# sensor.net
KiCad netlist of a schematic drawn in EAGLE
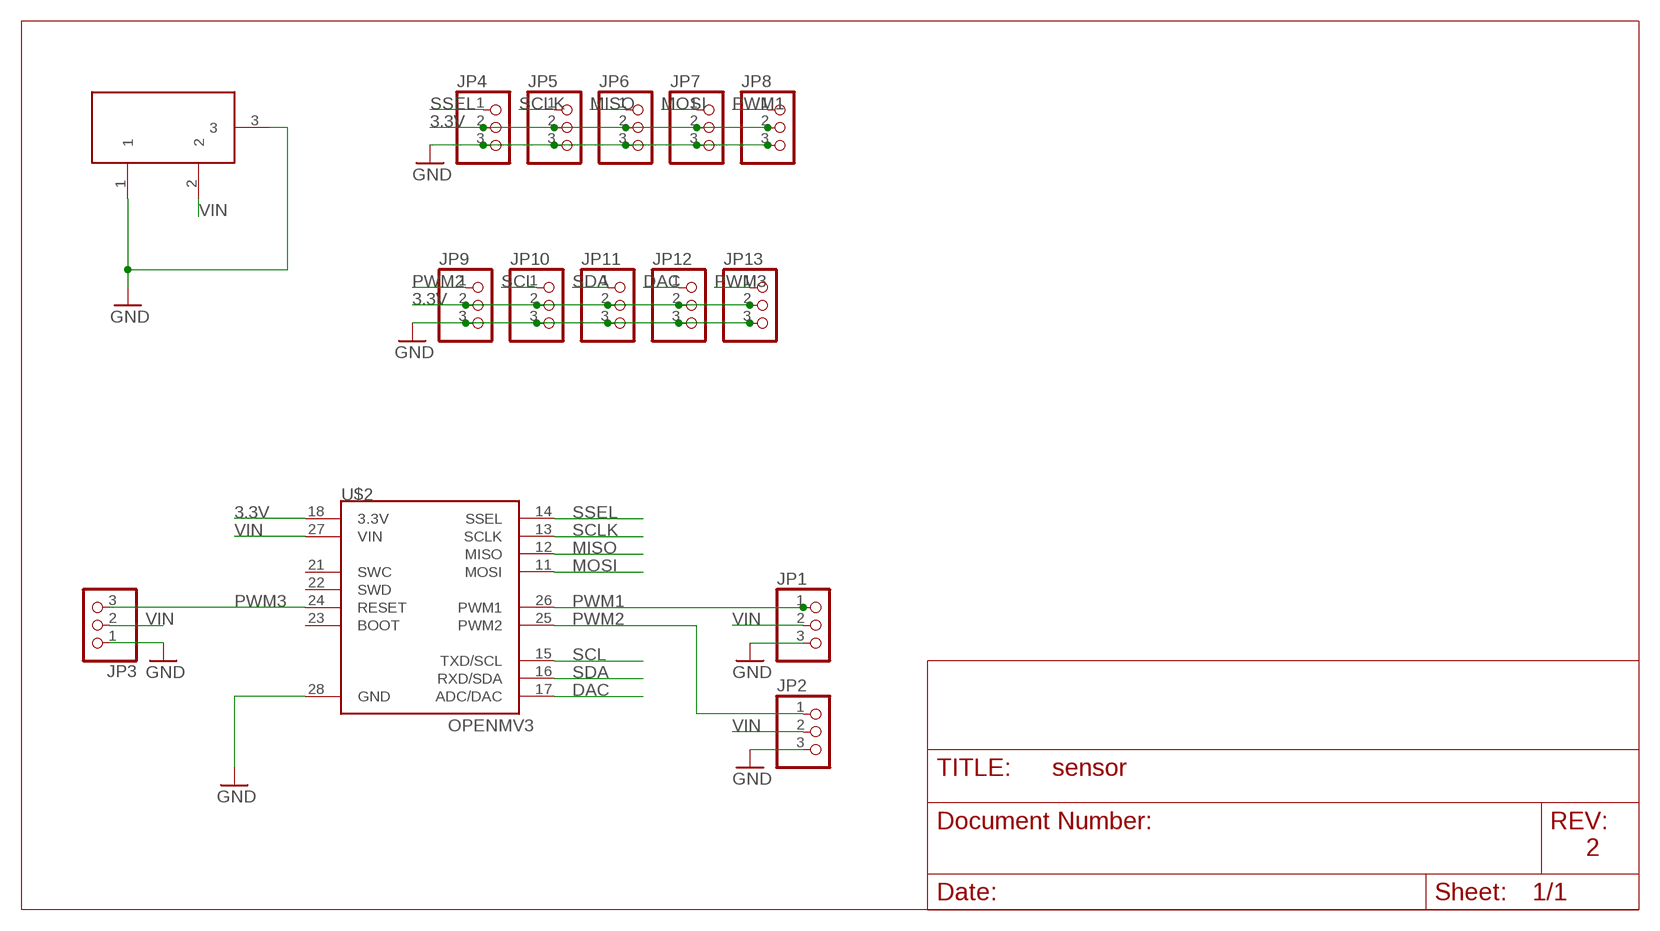
[diagram p0: schematic, sheet 1]

(export (version "E")
  (design (tool "Eeschema 10.0.6"))
  (components
    (comp (ref "JP1")
      (value "PINHEAD_PINHD-1X3")
      (footprint "eagle-import:PINHEAD_1X03")
      (libsource (lib "eagle-import") (part "PINHEAD_PINHD-1X3"))
    )
    (comp (ref "JP2")
      (value "PINHEAD_PINHD-1X3")
      (footprint "eagle-import:PINHEAD_1X03")
      (libsource (lib "eagle-import") (part "PINHEAD_PINHD-1X3"))
    )
    (comp (ref "JP3")
      (value "PINHEAD_PINHD-1X3")
      (footprint "eagle-import:PINHEAD_1X03")
      (libsource (lib "eagle-import") (part "PINHEAD_PINHD-1X3"))
    )
    (comp (ref "JP4")
      (value "PINHEAD_PINHD-1X3")
      (footprint "eagle-import:PINHEAD_1X03")
      (libsource (lib "eagle-import") (part "PINHEAD_PINHD-1X3"))
    )
    (comp (ref "JP5")
      (value "PINHEAD_PINHD-1X3")
      (footprint "eagle-import:PINHEAD_1X03")
      (libsource (lib "eagle-import") (part "PINHEAD_PINHD-1X3"))
    )
    (comp (ref "JP6")
      (value "PINHEAD_PINHD-1X3")
      (footprint "eagle-import:PINHEAD_1X03")
      (libsource (lib "eagle-import") (part "PINHEAD_PINHD-1X3"))
    )
    (comp (ref "JP7")
      (value "PINHEAD_PINHD-1X3")
      (footprint "eagle-import:PINHEAD_1X03")
      (libsource (lib "eagle-import") (part "PINHEAD_PINHD-1X3"))
    )
    (comp (ref "JP8")
      (value "PINHEAD_PINHD-1X3")
      (footprint "eagle-import:PINHEAD_1X03")
      (libsource (lib "eagle-import") (part "PINHEAD_PINHD-1X3"))
    )
    (comp (ref "JP9")
      (value "PINHEAD_PINHD-1X3")
      (footprint "eagle-import:PINHEAD_1X03")
      (libsource (lib "eagle-import") (part "PINHEAD_PINHD-1X3"))
    )
    (comp (ref "JP10")
      (value "PINHEAD_PINHD-1X3")
      (footprint "eagle-import:PINHEAD_1X03")
      (libsource (lib "eagle-import") (part "PINHEAD_PINHD-1X3"))
    )
    (comp (ref "JP11")
      (value "PINHEAD_PINHD-1X3")
      (footprint "eagle-import:PINHEAD_1X03")
      (libsource (lib "eagle-import") (part "PINHEAD_PINHD-1X3"))
    )
    (comp (ref "JP12")
      (value "PINHEAD_PINHD-1X3")
      (footprint "eagle-import:PINHEAD_1X03")
      (libsource (lib "eagle-import") (part "PINHEAD_PINHD-1X3"))
    )
    (comp (ref "JP13")
      (value "PINHEAD_PINHD-1X3")
      (footprint "eagle-import:PINHEAD_1X03")
      (libsource (lib "eagle-import") (part "PINHEAD_PINHD-1X3"))
    )
    (comp (ref "U$2")
      (value "OPENMV3")
      (footprint "eagle-import:OPENMV3")
      (libsource (lib "eagle-import") (part "OPENMV3"))
    )
    (comp (ref "X1")
      (value "DC21MMX")
      (footprint "eagle-import:DC-21MM")
      (libsource (lib "eagle-import") (part "DC21MMX"))
    )
  )
  (nets
    (net (code "1") (name "/3.3V") (class "Default")
      (node (ref "JP10") (pin "2") (pinfunction "2_2") (pintype "passive"))
      (node (ref "JP11") (pin "2") (pinfunction "2_2") (pintype "passive"))
      (node (ref "JP12") (pin "2") (pinfunction "2_2") (pintype "passive"))
      (node (ref "JP13") (pin "2") (pinfunction "2_2") (pintype "passive"))
      (node (ref "JP4") (pin "2") (pinfunction "2_2") (pintype "passive"))
      (node (ref "JP5") (pin "2") (pinfunction "2_2") (pintype "passive"))
      (node (ref "JP6") (pin "2") (pinfunction "2_2") (pintype "passive"))
      (node (ref "JP7") (pin "2") (pinfunction "2_2") (pintype "passive"))
      (node (ref "JP8") (pin "2") (pinfunction "2_2") (pintype "passive"))
      (node (ref "JP9") (pin "2") (pinfunction "2_2") (pintype "passive"))
      (node (ref "U$2") (pin "18") (pinfunction "3.3V_18") (pintype "power_in"))
    )
    (net (code "2") (name "/DAC") (class "Default")
      (node (ref "JP12") (pin "1") (pinfunction "1_1") (pintype "passive"))
      (node (ref "U$2") (pin "17") (pinfunction "ADC/DAC_17") (pintype "bidirectional"))
    )
    (net (code "3") (name "/MISO") (class "Default")
      (node (ref "JP6") (pin "1") (pinfunction "1_1") (pintype "passive"))
      (node (ref "U$2") (pin "12") (pinfunction "MISO_12") (pintype "bidirectional"))
    )
    (net (code "4") (name "/MOSI") (class "Default")
      (node (ref "JP7") (pin "1") (pinfunction "1_1") (pintype "passive"))
      (node (ref "U$2") (pin "11") (pinfunction "MOSI_11") (pintype "bidirectional"))
    )
    (net (code "5") (name "/PWM1") (class "Default")
      (node (ref "JP1") (pin "1") (pinfunction "1_1") (pintype "passive"))
      (node (ref "JP8") (pin "1") (pinfunction "1_1") (pintype "passive"))
      (node (ref "U$2") (pin "26") (pinfunction "PWM1_26") (pintype "bidirectional"))
    )
    (net (code "6") (name "/PWM2") (class "Default")
      (node (ref "JP2") (pin "1") (pinfunction "1_1") (pintype "passive"))
      (node (ref "JP9") (pin "1") (pinfunction "1_1") (pintype "passive"))
      (node (ref "U$2") (pin "25") (pinfunction "PWM2_25") (pintype "bidirectional"))
    )
    (net (code "7") (name "/PWM3") (class "Default")
      (node (ref "JP13") (pin "1") (pinfunction "1_1") (pintype "passive"))
      (node (ref "JP3") (pin "3") (pinfunction "3_3") (pintype "passive"))
      (node (ref "U$2") (pin "24") (pinfunction "RESET_24") (pintype "bidirectional"))
    )
    (net (code "8") (name "/SCL") (class "Default")
      (node (ref "JP10") (pin "1") (pinfunction "1_1") (pintype "passive"))
      (node (ref "U$2") (pin "15") (pinfunction "TXD/SCL_15") (pintype "bidirectional"))
    )
    (net (code "9") (name "/SCLK") (class "Default")
      (node (ref "JP5") (pin "1") (pinfunction "1_1") (pintype "passive"))
      (node (ref "U$2") (pin "13") (pinfunction "SCLK_13") (pintype "bidirectional"))
    )
    (net (code "10") (name "/SDA") (class "Default")
      (node (ref "JP11") (pin "1") (pinfunction "1_1") (pintype "passive"))
      (node (ref "U$2") (pin "16") (pinfunction "RXD/SDA_16") (pintype "bidirectional"))
    )
    (net (code "11") (name "/SSEL") (class "Default")
      (node (ref "JP4") (pin "1") (pinfunction "1_1") (pintype "passive"))
      (node (ref "U$2") (pin "14") (pinfunction "SSEL_14") (pintype "bidirectional"))
    )
    (net (code "12") (name "/VIN") (class "Default")
      (node (ref "JP1") (pin "2") (pinfunction "2_2") (pintype "passive"))
      (node (ref "JP2") (pin "2") (pinfunction "2_2") (pintype "passive"))
      (node (ref "JP3") (pin "2") (pinfunction "2_2") (pintype "passive"))
      (node (ref "U$2") (pin "27") (pinfunction "VIN_27") (pintype "power_in"))
      (node (ref "X1") (pin "2") (pinfunction "2_2") (pintype "power_in"))
    )
    (net (code "13") (name "GND") (class "Default")
      (node (ref "JP1") (pin "3") (pinfunction "3_3") (pintype "passive"))
      (node (ref "JP10") (pin "3") (pinfunction "3_3") (pintype "passive"))
      (node (ref "JP11") (pin "3") (pinfunction "3_3") (pintype "passive"))
      (node (ref "JP12") (pin "3") (pinfunction "3_3") (pintype "passive"))
      (node (ref "JP13") (pin "3") (pinfunction "3_3") (pintype "passive"))
      (node (ref "JP2") (pin "3") (pinfunction "3_3") (pintype "passive"))
      (node (ref "JP3") (pin "1") (pinfunction "1_1") (pintype "passive"))
      (node (ref "JP4") (pin "3") (pinfunction "3_3") (pintype "passive"))
      (node (ref "JP5") (pin "3") (pinfunction "3_3") (pintype "passive"))
      (node (ref "JP6") (pin "3") (pinfunction "3_3") (pintype "passive"))
      (node (ref "JP7") (pin "3") (pinfunction "3_3") (pintype "passive"))
      (node (ref "JP8") (pin "3") (pinfunction "3_3") (pintype "passive"))
      (node (ref "JP9") (pin "3") (pinfunction "3_3") (pintype "passive"))
      (node (ref "U$2") (pin "28") (pinfunction "GND_28") (pintype "power_in"))
      (node (ref "X1") (pin "1") (pinfunction "1_1") (pintype "power_in"))
      (node (ref "X1") (pin "3") (pinfunction "3_3") (pintype "power_in"))
    )
    (net (code "14") (name "unconnected-(U$2-BOOT-Pad23)") (class "Default")
      (node (ref "U$2") (pin "23") (pinfunction "BOOT_23") (pintype "bidirectional"))
    )
    (net (code "15") (name "unconnected-(U$2-SWC-Pad21)") (class "Default")
      (node (ref "U$2") (pin "21") (pinfunction "SWC_21") (pintype "bidirectional"))
    )
    (net (code "16") (name "unconnected-(U$2-SWD-Pad22)") (class "Default")
      (node (ref "U$2") (pin "22") (pinfunction "SWD_22") (pintype "bidirectional"))
    )
  )
)
